# Devi.net
KiCad netlist of a schematic drawn in EAGLE
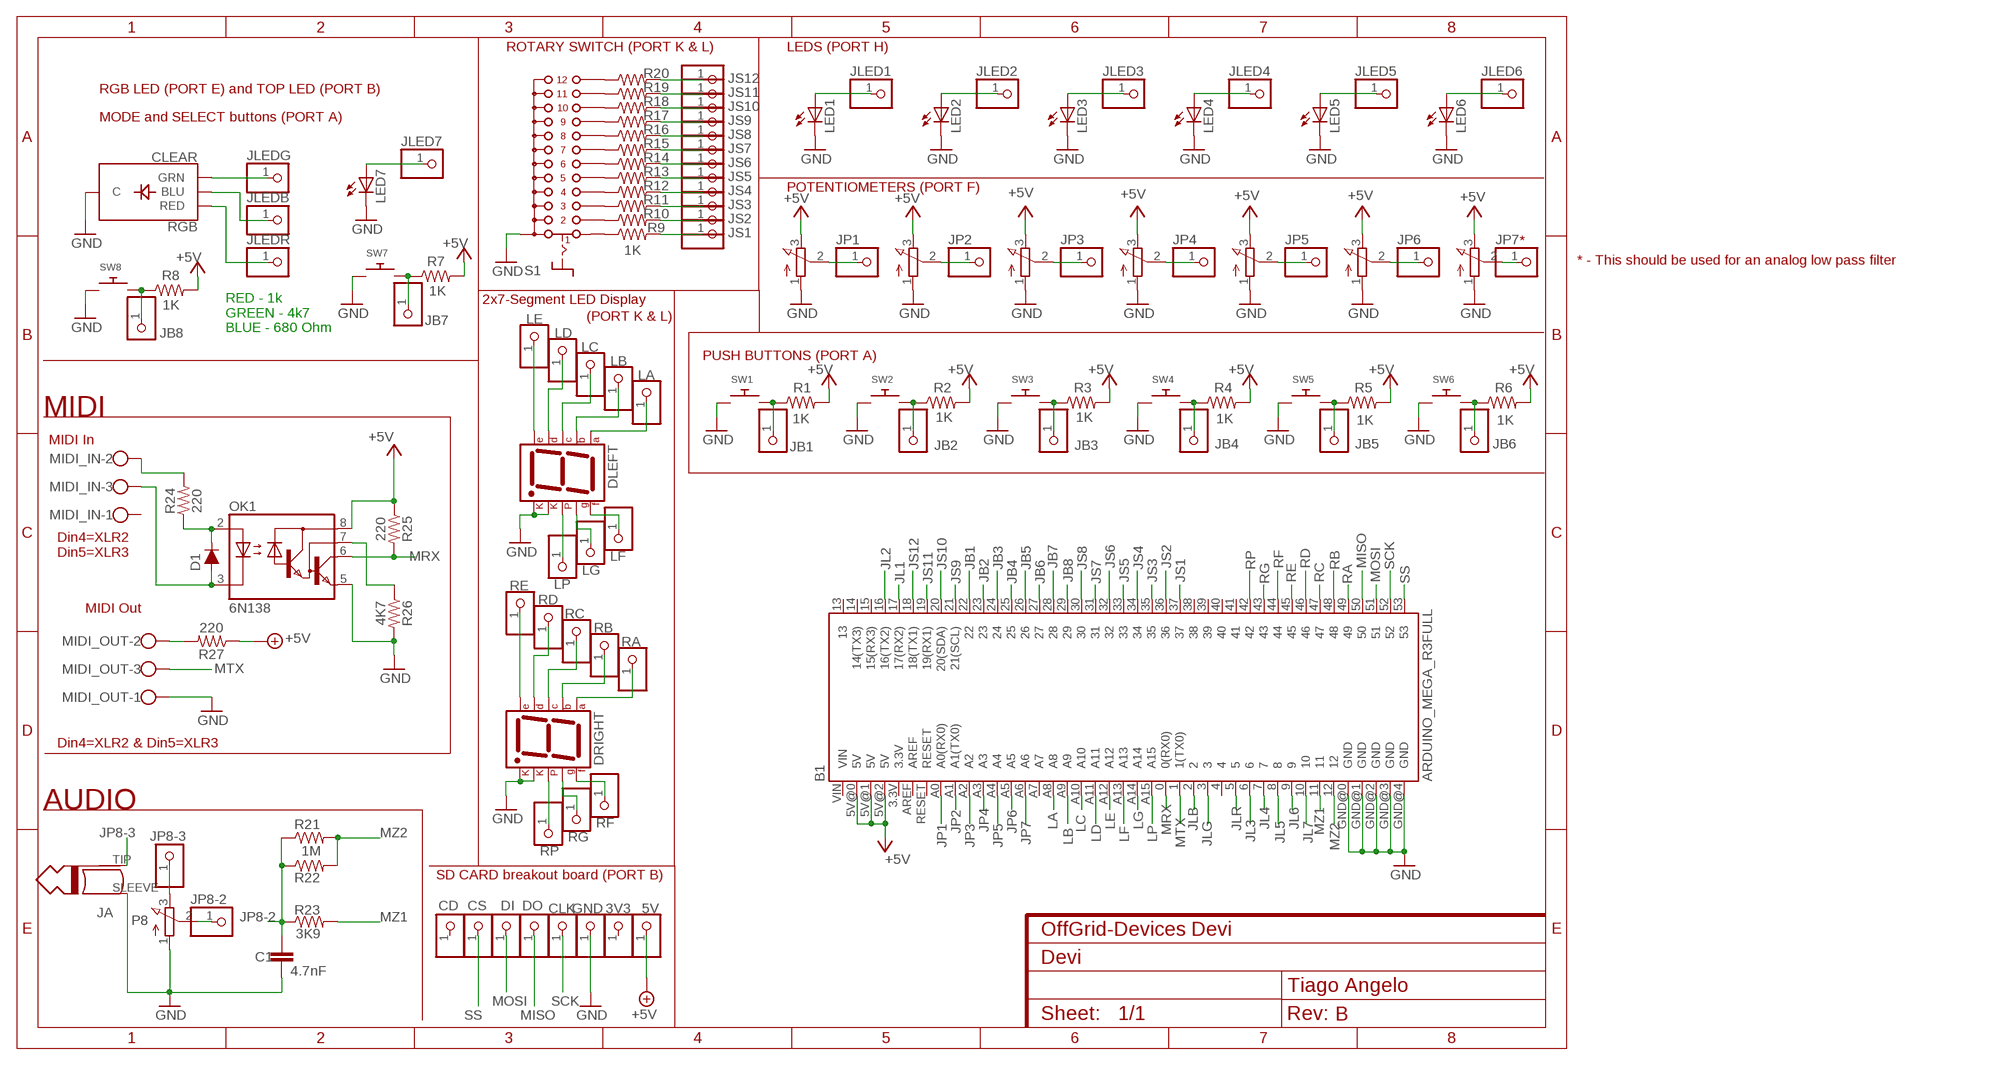
[diagram p0: schematic, sheet 1]

(export (version "E")
  (design (tool "Eeschema 10.0.6"))
  (components
    (comp (ref "3V3")
      (value "PINHD-1X1CB")
      (footprint "eagle-import:1X01-CLEANBIG")
      (libsource (lib "eagle-import") (part "PINHD-1X1CB"))
    )
    (comp (ref "5V")
      (value "PINHD-1X1CB")
      (footprint "eagle-import:1X01-CLEANBIG")
      (libsource (lib "eagle-import") (part "PINHD-1X1CB"))
    )
    (comp (ref "B1")
      (value "ARDUINO_MEGA_R3FULL")
      (footprint "eagle-import:ARDUINO_MEGA")
      (libsource (lib "eagle-import") (part "ARDUINO_MEGA_R3FULL"))
    )
    (comp (ref "C1")
      (value "4.7nF")
      (footprint "eagle-import:C050-025X075")
      (libsource (lib "eagle-import") (part "C-EU050-025X075"))
    )
    (comp (ref "CD")
      (value "PINHD-1X1CB")
      (footprint "eagle-import:1X01-CLEANBIG")
      (libsource (lib "eagle-import") (part "PINHD-1X1CB"))
    )
    (comp (ref "CLK")
      (value "PINHD-1X1CB")
      (footprint "eagle-import:1X01-CLEANBIG")
      (libsource (lib "eagle-import") (part "PINHD-1X1CB"))
    )
    (comp (ref "CS")
      (value "PINHD-1X1CB")
      (footprint "eagle-import:1X01-CLEANBIG")
      (libsource (lib "eagle-import") (part "PINHD-1X1CB"))
    )
    (comp (ref "D1")
      (value "200mA/100V/1V")
      (footprint "eagle-import:DIODE-1N4148")
      (libsource (lib "eagle-import") (part "DIODE-1N4148"))
    )
    (comp (ref "DI")
      (value "PINHD-1X1CB")
      (footprint "eagle-import:1X01-CLEANBIG")
      (libsource (lib "eagle-import") (part "PINHD-1X1CB"))
    )
    (comp (ref "DLEFT")
      (value "7SEG-CK")
      (footprint "eagle-import:7SEG-13")
      (libsource (lib "eagle-import") (part "7SEG-CK"))
    )
    (comp (ref "DO")
      (value "PINHD-1X1CB")
      (footprint "eagle-import:1X01-CLEANBIG")
      (libsource (lib "eagle-import") (part "PINHD-1X1CB"))
    )
    (comp (ref "DRIGHT")
      (value "7SEG-CK")
      (footprint "eagle-import:7SEG-13")
      (libsource (lib "eagle-import") (part "7SEG-CK"))
    )
    (comp (ref "GND")
      (value "PINHD-1X1CB")
      (footprint "eagle-import:1X01-CLEANBIG")
      (libsource (lib "eagle-import") (part "PINHD-1X1CB"))
    )
    (comp (ref "JA")
      (value "MONO_PLUG")
      (footprint "eagle-import:TWO_PADS")
      (libsource (lib "eagle-import") (part "MONO_PLUG"))
    )
    (comp (ref "JB1")
      (value "PINHD-1X1CB")
      (footprint "eagle-import:1X01-CLEANBIG")
      (libsource (lib "eagle-import") (part "PINHD-1X1CB"))
    )
    (comp (ref "JB2")
      (value "PINHD-1X1CB")
      (footprint "eagle-import:1X01-CLEANBIG")
      (libsource (lib "eagle-import") (part "PINHD-1X1CB"))
    )
    (comp (ref "JB3")
      (value "PINHD-1X1CB")
      (footprint "eagle-import:1X01-CLEANBIG")
      (libsource (lib "eagle-import") (part "PINHD-1X1CB"))
    )
    (comp (ref "JB4")
      (value "PINHD-1X1CB")
      (footprint "eagle-import:1X01-CLEANBIG")
      (libsource (lib "eagle-import") (part "PINHD-1X1CB"))
    )
    (comp (ref "JB5")
      (value "PINHD-1X1CB")
      (footprint "eagle-import:1X01-CLEANBIG")
      (libsource (lib "eagle-import") (part "PINHD-1X1CB"))
    )
    (comp (ref "JB6")
      (value "PINHD-1X1CB")
      (footprint "eagle-import:1X01-CLEANBIG")
      (libsource (lib "eagle-import") (part "PINHD-1X1CB"))
    )
    (comp (ref "JB7")
      (value "PINHD-1X1CB")
      (footprint "eagle-import:1X01-CLEANBIG")
      (libsource (lib "eagle-import") (part "PINHD-1X1CB"))
    )
    (comp (ref "JB8")
      (value "PINHD-1X1CB")
      (footprint "eagle-import:1X01-CLEANBIG")
      (libsource (lib "eagle-import") (part "PINHD-1X1CB"))
    )
    (comp (ref "JLED1")
      (value "PINHD-1X1CB")
      (footprint "eagle-import:1X01-CLEANBIG")
      (libsource (lib "eagle-import") (part "PINHD-1X1CB"))
    )
    (comp (ref "JLED2")
      (value "PINHD-1X1CB")
      (footprint "eagle-import:1X01-CLEANBIG")
      (libsource (lib "eagle-import") (part "PINHD-1X1CB"))
    )
    (comp (ref "JLED3")
      (value "PINHD-1X1CB")
      (footprint "eagle-import:1X01-CLEANBIG")
      (libsource (lib "eagle-import") (part "PINHD-1X1CB"))
    )
    (comp (ref "JLED4")
      (value "PINHD-1X1CB")
      (footprint "eagle-import:1X01-CLEANBIG")
      (libsource (lib "eagle-import") (part "PINHD-1X1CB"))
    )
    (comp (ref "JLED5")
      (value "PINHD-1X1CB")
      (footprint "eagle-import:1X01-CLEANBIG")
      (libsource (lib "eagle-import") (part "PINHD-1X1CB"))
    )
    (comp (ref "JLED6")
      (value "PINHD-1X1CB")
      (footprint "eagle-import:1X01-CLEANBIG")
      (libsource (lib "eagle-import") (part "PINHD-1X1CB"))
    )
    (comp (ref "JLED7")
      (value "PINHD-1X1CB")
      (footprint "eagle-import:1X01-CLEANBIG")
      (libsource (lib "eagle-import") (part "PINHD-1X1CB"))
    )
    (comp (ref "JLEDB")
      (value "PINHD-1X1CB")
      (footprint "eagle-import:1X01-CLEANBIG")
      (libsource (lib "eagle-import") (part "PINHD-1X1CB"))
    )
    (comp (ref "JLEDG")
      (value "PINHD-1X1CB")
      (footprint "eagle-import:1X01-CLEANBIG")
      (libsource (lib "eagle-import") (part "PINHD-1X1CB"))
    )
    (comp (ref "JLEDR")
      (value "PINHD-1X1CB")
      (footprint "eagle-import:1X01-CLEANBIG")
      (libsource (lib "eagle-import") (part "PINHD-1X1CB"))
    )
    (comp (ref "JP1")
      (value "PINHD-1X1CB")
      (footprint "eagle-import:1X01-CLEANBIG")
      (libsource (lib "eagle-import") (part "PINHD-1X1CB"))
    )
    (comp (ref "JP2")
      (value "PINHD-1X1CB")
      (footprint "eagle-import:1X01-CLEANBIG")
      (libsource (lib "eagle-import") (part "PINHD-1X1CB"))
    )
    (comp (ref "JP3")
      (value "PINHD-1X1CB")
      (footprint "eagle-import:1X01-CLEANBIG")
      (libsource (lib "eagle-import") (part "PINHD-1X1CB"))
    )
    (comp (ref "JP4")
      (value "PINHD-1X1CB")
      (footprint "eagle-import:1X01-CLEANBIG")
      (libsource (lib "eagle-import") (part "PINHD-1X1CB"))
    )
    (comp (ref "JP5")
      (value "PINHD-1X1CB")
      (footprint "eagle-import:1X01-CLEANBIG")
      (libsource (lib "eagle-import") (part "PINHD-1X1CB"))
    )
    (comp (ref "JP6")
      (value "PINHD-1X1CB")
      (footprint "eagle-import:1X01-CLEANBIG")
      (libsource (lib "eagle-import") (part "PINHD-1X1CB"))
    )
    (comp (ref "JP7")
      (value "PINHD-1X1CB")
      (footprint "eagle-import:1X01-CLEANBIG")
      (libsource (lib "eagle-import") (part "PINHD-1X1CB"))
    )
    (comp (ref "JP8-2")
      (value "PINHD-1X1CB")
      (footprint "eagle-import:1X01-CLEANBIG")
      (libsource (lib "eagle-import") (part "PINHD-1X1CB"))
    )
    (comp (ref "JP8-3")
      (value "PINHD-1X1CB")
      (footprint "eagle-import:1X01-CLEANBIG")
      (libsource (lib "eagle-import") (part "PINHD-1X1CB"))
    )
    (comp (ref "JS1")
      (value "PINHD-1X1CB")
      (footprint "eagle-import:1X01-CLEANBIG")
      (libsource (lib "eagle-import") (part "PINHD-1X1CB"))
    )
    (comp (ref "JS2")
      (value "PINHD-1X1CB")
      (footprint "eagle-import:1X01-CLEANBIG")
      (libsource (lib "eagle-import") (part "PINHD-1X1CB"))
    )
    (comp (ref "JS3")
      (value "PINHD-1X1CB")
      (footprint "eagle-import:1X01-CLEANBIG")
      (libsource (lib "eagle-import") (part "PINHD-1X1CB"))
    )
    (comp (ref "JS4")
      (value "PINHD-1X1CB")
      (footprint "eagle-import:1X01-CLEANBIG")
      (libsource (lib "eagle-import") (part "PINHD-1X1CB"))
    )
    (comp (ref "JS5")
      (value "PINHD-1X1CB")
      (footprint "eagle-import:1X01-CLEANBIG")
      (libsource (lib "eagle-import") (part "PINHD-1X1CB"))
    )
    (comp (ref "JS6")
      (value "PINHD-1X1CB")
      (footprint "eagle-import:1X01-CLEANBIG")
      (libsource (lib "eagle-import") (part "PINHD-1X1CB"))
    )
    (comp (ref "JS7")
      (value "PINHD-1X1CB")
      (footprint "eagle-import:1X01-CLEANBIG")
      (libsource (lib "eagle-import") (part "PINHD-1X1CB"))
    )
    (comp (ref "JS8")
      (value "PINHD-1X1CB")
      (footprint "eagle-import:1X01-CLEANBIG")
      (libsource (lib "eagle-import") (part "PINHD-1X1CB"))
    )
    (comp (ref "JS9")
      (value "PINHD-1X1CB")
      (footprint "eagle-import:1X01-CLEANBIG")
      (libsource (lib "eagle-import") (part "PINHD-1X1CB"))
    )
    (comp (ref "JS10")
      (value "PINHD-1X1CB")
      (footprint "eagle-import:1X01-CLEANBIG")
      (libsource (lib "eagle-import") (part "PINHD-1X1CB"))
    )
    (comp (ref "JS11")
      (value "PINHD-1X1CB")
      (footprint "eagle-import:1X01-CLEANBIG")
      (libsource (lib "eagle-import") (part "PINHD-1X1CB"))
    )
    (comp (ref "JS12")
      (value "PINHD-1X1CB")
      (footprint "eagle-import:1X01-CLEANBIG")
      (libsource (lib "eagle-import") (part "PINHD-1X1CB"))
    )
    (comp (ref "LA")
      (value "PINHD-1X1CB")
      (footprint "eagle-import:1X01-CLEANBIG")
      (libsource (lib "eagle-import") (part "PINHD-1X1CB"))
    )
    (comp (ref "LB")
      (value "PINHD-1X1CB")
      (footprint "eagle-import:1X01-CLEANBIG")
      (libsource (lib "eagle-import") (part "PINHD-1X1CB"))
    )
    (comp (ref "LC")
      (value "PINHD-1X1CB")
      (footprint "eagle-import:1X01-CLEANBIG")
      (libsource (lib "eagle-import") (part "PINHD-1X1CB"))
    )
    (comp (ref "LD")
      (value "PINHD-1X1CB")
      (footprint "eagle-import:1X01-CLEANBIG")
      (libsource (lib "eagle-import") (part "PINHD-1X1CB"))
    )
    (comp (ref "LE")
      (value "PINHD-1X1CB")
      (footprint "eagle-import:1X01-CLEANBIG")
      (libsource (lib "eagle-import") (part "PINHD-1X1CB"))
    )
    (comp (ref "LED1")
      (value "LED3MM")
      (footprint "eagle-import:LED3MM")
      (libsource (lib "eagle-import") (part "LED3MM"))
    )
    (comp (ref "LED2")
      (value "LED3MM")
      (footprint "eagle-import:LED3MM")
      (libsource (lib "eagle-import") (part "LED3MM"))
    )
    (comp (ref "LED3")
      (value "LED3MM")
      (footprint "eagle-import:LED3MM")
      (libsource (lib "eagle-import") (part "LED3MM"))
    )
    (comp (ref "LED4")
      (value "LED3MM")
      (footprint "eagle-import:LED3MM")
      (libsource (lib "eagle-import") (part "LED3MM"))
    )
    (comp (ref "LED5")
      (value "LED3MM")
      (footprint "eagle-import:LED3MM")
      (libsource (lib "eagle-import") (part "LED3MM"))
    )
    (comp (ref "LED6")
      (value "LED3MM")
      (footprint "eagle-import:LED3MM")
      (libsource (lib "eagle-import") (part "LED3MM"))
    )
    (comp (ref "LED7")
      (value "LED3MM")
      (footprint "eagle-import:LED3MM")
      (libsource (lib "eagle-import") (part "LED3MM"))
    )
    (comp (ref "LF")
      (value "PINHD-1X1CB")
      (footprint "eagle-import:1X01-CLEANBIG")
      (libsource (lib "eagle-import") (part "PINHD-1X1CB"))
    )
    (comp (ref "LG")
      (value "PINHD-1X1CB")
      (footprint "eagle-import:1X01-CLEANBIG")
      (libsource (lib "eagle-import") (part "PINHD-1X1CB"))
    )
    (comp (ref "LP")
      (value "PINHD-1X1CB")
      (footprint "eagle-import:1X01-CLEANBIG")
      (libsource (lib "eagle-import") (part "PINHD-1X1CB"))
    )
    (comp (ref "MIDI_IN")
      (value "W237-103")
      (footprint "eagle-import:W237-103")
      (fields (field (name "MPN") "237-103"))
      (libsource (lib "eagle-import") (part "W237-103"))
    )
    (comp (ref "MIDI_OUT")
      (value "W237-103")
      (footprint "eagle-import:W237-103")
      (fields (field (name "MPN") "237-103"))
      (libsource (lib "eagle-import") (part "W237-103"))
    )
    (comp (ref "OK1")
      (value "6N138")
      (footprint "eagle-import:DIL08")
      (fields (field (name "MF") "VISHAY/TELEFUNKEN"))
      (libsource (lib "eagle-import") (part "6N138"))
    )
    (comp (ref "P1")
      (value "3RP/1610N")
      (footprint "eagle-import:3RP_1610N")
      (libsource (lib "eagle-import") (part "3RP/1610N"))
    )
    (comp (ref "P2")
      (value "3RP/1610N")
      (footprint "eagle-import:3RP_1610N")
      (libsource (lib "eagle-import") (part "3RP/1610N"))
    )
    (comp (ref "P3")
      (value "3RP/1610N")
      (footprint "eagle-import:3RP_1610N")
      (libsource (lib "eagle-import") (part "3RP/1610N"))
    )
    (comp (ref "P4")
      (value "3RP/1610N")
      (footprint "eagle-import:3RP_1610N")
      (libsource (lib "eagle-import") (part "3RP/1610N"))
    )
    (comp (ref "P5")
      (value "3RP/1610N")
      (footprint "eagle-import:3RP_1610N")
      (libsource (lib "eagle-import") (part "3RP/1610N"))
    )
    (comp (ref "P6")
      (value "3RP/1610N")
      (footprint "eagle-import:3RP_1610N")
      (libsource (lib "eagle-import") (part "3RP/1610N"))
    )
    (comp (ref "P7")
      (value "3RP/1610N")
      (footprint "eagle-import:3RP_1610N")
      (libsource (lib "eagle-import") (part "3RP/1610N"))
    )
    (comp (ref "P8")
      (value "3RP/1610N")
      (footprint "eagle-import:3RP_1610N")
      (libsource (lib "eagle-import") (part "3RP/1610N"))
    )
    (comp (ref "R1")
      (value "1K")
      (footprint "eagle-import:AXIAL-0.3")
      (libsource (lib "eagle-import") (part "1KOHM-HORIZ-1/4W-5%"))
    )
    (comp (ref "R2")
      (value "1K")
      (footprint "eagle-import:AXIAL-0.3")
      (libsource (lib "eagle-import") (part "1KOHM-HORIZ-1/4W-5%"))
    )
    (comp (ref "R3")
      (value "1K")
      (footprint "eagle-import:AXIAL-0.3")
      (libsource (lib "eagle-import") (part "1KOHM-HORIZ-1/4W-5%"))
    )
    (comp (ref "R4")
      (value "1K")
      (footprint "eagle-import:AXIAL-0.3")
      (libsource (lib "eagle-import") (part "1KOHM-HORIZ-1/4W-5%"))
    )
    (comp (ref "R5")
      (value "1K")
      (footprint "eagle-import:AXIAL-0.3")
      (libsource (lib "eagle-import") (part "1KOHM-HORIZ-1/4W-5%"))
    )
    (comp (ref "R6")
      (value "1K")
      (footprint "eagle-import:AXIAL-0.3")
      (libsource (lib "eagle-import") (part "1KOHM-HORIZ-1/4W-5%"))
    )
    (comp (ref "R7")
      (value "1K")
      (footprint "eagle-import:AXIAL-0.3")
      (libsource (lib "eagle-import") (part "1KOHM-HORIZ-1/4W-5%"))
    )
    (comp (ref "R8")
      (value "1K")
      (footprint "eagle-import:AXIAL-0.3")
      (libsource (lib "eagle-import") (part "1KOHM-HORIZ-1/4W-5%"))
    )
    (comp (ref "R9")
      (value "1K")
      (footprint "eagle-import:AXIAL-0.3")
      (libsource (lib "eagle-import") (part "1KOHM-HORIZ-1/4W-5%"))
    )
    (comp (ref "R10")
      (value "1K")
      (footprint "eagle-import:AXIAL-0.3")
      (libsource (lib "eagle-import") (part "1KOHM-HORIZ-1/4W-5%"))
    )
    (comp (ref "R11")
      (value "1K")
      (footprint "eagle-import:AXIAL-0.3")
      (libsource (lib "eagle-import") (part "1KOHM-HORIZ-1/4W-5%"))
    )
    (comp (ref "R12")
      (value "1K")
      (footprint "eagle-import:AXIAL-0.3")
      (libsource (lib "eagle-import") (part "1KOHM-HORIZ-1/4W-5%"))
    )
    (comp (ref "R13")
      (value "1K")
      (footprint "eagle-import:AXIAL-0.3")
      (libsource (lib "eagle-import") (part "1KOHM-HORIZ-1/4W-5%"))
    )
    (comp (ref "R14")
      (value "1K")
      (footprint "eagle-import:AXIAL-0.3")
      (libsource (lib "eagle-import") (part "1KOHM-HORIZ-1/4W-5%"))
    )
    (comp (ref "R15")
      (value "1K")
      (footprint "eagle-import:AXIAL-0.3")
      (libsource (lib "eagle-import") (part "1KOHM-HORIZ-1/4W-5%"))
    )
    (comp (ref "R16")
      (value "1K")
      (footprint "eagle-import:AXIAL-0.3")
      (libsource (lib "eagle-import") (part "1KOHM-HORIZ-1/4W-5%"))
    )
    (comp (ref "R17")
      (value "1K")
      (footprint "eagle-import:AXIAL-0.3")
      (libsource (lib "eagle-import") (part "1KOHM-HORIZ-1/4W-5%"))
    )
    (comp (ref "R18")
      (value "1K")
      (footprint "eagle-import:AXIAL-0.3")
      (libsource (lib "eagle-import") (part "1KOHM-HORIZ-1/4W-5%"))
    )
    (comp (ref "R19")
      (value "1K")
      (footprint "eagle-import:AXIAL-0.3")
      (libsource (lib "eagle-import") (part "1KOHM-HORIZ-1/4W-5%"))
    )
    (comp (ref "R20")
      (value "1K")
      (footprint "eagle-import:AXIAL-0.3")
      (libsource (lib "eagle-import") (part "1KOHM-HORIZ-1/4W-5%"))
    )
    (comp (ref "R21")
      (value "1M")
      (footprint "eagle-import:AXIAL-0.3")
      (libsource (lib "eagle-import") (part "1KOHM-HORIZ-1/4W-5%"))
    )
    (comp (ref "R22")
      (value "1M")
      (footprint "eagle-import:AXIAL-0.3")
      (libsource (lib "eagle-import") (part "1KOHM-HORIZ-1/4W-5%"))
    )
    (comp (ref "R23")
      (value "3K9")
      (footprint "eagle-import:AXIAL-0.3")
      (libsource (lib "eagle-import") (part "1KOHM-HORIZ-1/4W-5%"))
    )
    (comp (ref "R24")
      (value "220")
      (footprint "eagle-import:AXIAL-0.3")
      (libsource (lib "eagle-import") (part "1KOHM-HORIZ-1/4W-5%"))
    )
    (comp (ref "R25")
      (value "220")
      (footprint "eagle-import:AXIAL-0.3")
      (libsource (lib "eagle-import") (part "1KOHM-HORIZ-1/4W-5%"))
    )
    (comp (ref "R26")
      (value "4K7")
      (footprint "eagle-import:AXIAL-0.3")
      (libsource (lib "eagle-import") (part "1KOHM-HORIZ-1/4W-5%"))
    )
    (comp (ref "R27")
      (value "220")
      (footprint "eagle-import:AXIAL-0.3")
      (libsource (lib "eagle-import") (part "1KOHM-HORIZ-1/4W-5%"))
    )
    (comp (ref "RA")
      (value "PINHD-1X1CB")
      (footprint "eagle-import:1X01-CLEANBIG")
      (libsource (lib "eagle-import") (part "PINHD-1X1CB"))
    )
    (comp (ref "RB")
      (value "PINHD-1X1CB")
      (footprint "eagle-import:1X01-CLEANBIG")
      (libsource (lib "eagle-import") (part "PINHD-1X1CB"))
    )
    (comp (ref "RC")
      (value "PINHD-1X1CB")
      (footprint "eagle-import:1X01-CLEANBIG")
      (libsource (lib "eagle-import") (part "PINHD-1X1CB"))
    )
    (comp (ref "RD")
      (value "PINHD-1X1CB")
      (footprint "eagle-import:1X01-CLEANBIG")
      (libsource (lib "eagle-import") (part "PINHD-1X1CB"))
    )
    (comp (ref "RE")
      (value "PINHD-1X1CB")
      (footprint "eagle-import:1X01-CLEANBIG")
      (libsource (lib "eagle-import") (part "PINHD-1X1CB"))
    )
    (comp (ref "RF")
      (value "PINHD-1X1CB")
      (footprint "eagle-import:1X01-CLEANBIG")
      (libsource (lib "eagle-import") (part "PINHD-1X1CB"))
    )
    (comp (ref "RG")
      (value "PINHD-1X1CB")
      (footprint "eagle-import:1X01-CLEANBIG")
      (libsource (lib "eagle-import") (part "PINHD-1X1CB"))
    )
    (comp (ref "RGB")
      (value "CLEAR")
      (footprint "eagle-import:LED-RGB-THRU")
      (libsource (lib "eagle-import") (part "LED-RGB-CCCLEAR"))
    )
    (comp (ref "RP")
      (value "PINHD-1X1CB")
      (footprint "eagle-import:1X01-CLEANBIG")
      (libsource (lib "eagle-import") (part "PINHD-1X1CB"))
    )
    (comp (ref "S1")
      (value "CK101X12")
      (footprint "eagle-import:CK101X12")
      (libsource (lib "eagle-import") (part "CK101X12"))
    )
    (comp (ref "SW1")
      (value "SWITCH_PUSHBUTTONEVQ-PE")
      (footprint "eagle-import:TACT_PANA-EVQ")
      (libsource (lib "eagle-import") (part "SWITCH_PUSHBUTTONEVQ-PE"))
    )
    (comp (ref "SW2")
      (value "SWITCH_PUSHBUTTONEVQ-PE")
      (footprint "eagle-import:TACT_PANA-EVQ")
      (libsource (lib "eagle-import") (part "SWITCH_PUSHBUTTONEVQ-PE"))
    )
    (comp (ref "SW3")
      (value "SWITCH_PUSHBUTTONEVQ-PE")
      (footprint "eagle-import:TACT_PANA-EVQ")
      (libsource (lib "eagle-import") (part "SWITCH_PUSHBUTTONEVQ-PE"))
    )
    (comp (ref "SW4")
      (value "SWITCH_PUSHBUTTONEVQ-PE")
      (footprint "eagle-import:TACT_PANA-EVQ")
      (libsource (lib "eagle-import") (part "SWITCH_PUSHBUTTONEVQ-PE"))
    )
    (comp (ref "SW5")
      (value "SWITCH_PUSHBUTTONEVQ-PE")
      (footprint "eagle-import:TACT_PANA-EVQ")
      (libsource (lib "eagle-import") (part "SWITCH_PUSHBUTTONEVQ-PE"))
    )
    (comp (ref "SW6")
      (value "SWITCH_PUSHBUTTONEVQ-PE")
      (footprint "eagle-import:TACT_PANA-EVQ")
      (libsource (lib "eagle-import") (part "SWITCH_PUSHBUTTONEVQ-PE"))
    )
    (comp (ref "SW7")
      (value "SWITCH_PUSHBUTTONEVQ-PE")
      (footprint "eagle-import:TACT_PANA-EVQ")
      (libsource (lib "eagle-import") (part "SWITCH_PUSHBUTTONEVQ-PE"))
    )
    (comp (ref "SW8")
      (value "SWITCH_PUSHBUTTONEVQ-PE")
      (footprint "eagle-import:TACT_PANA-EVQ")
      (libsource (lib "eagle-import") (part "SWITCH_PUSHBUTTONEVQ-PE"))
    )
  )
  (nets
    (net (code "1") (name "+5V") (class "Default")
      (node (ref "5V") (pin "1") (pinfunction "1_1") (pintype "passive"))
      (node (ref "B1") (pin "5V@0") (pinfunction "5V_5V@0") (pintype "bidirectional"))
      (node (ref "B1") (pin "5V@1") (pinfunction "5V_5V@1") (pintype "bidirectional"))
      (node (ref "B1") (pin "5V@2") (pinfunction "5V_5V@2") (pintype "bidirectional"))
      (node (ref "OK1") (pin "8") (pinfunction "VCC_8") (pintype "passive"))
      (node (ref "P1") (pin "3") (pinfunction "E_3") (pintype "passive"))
      (node (ref "P2") (pin "3") (pinfunction "E_3") (pintype "passive"))
      (node (ref "P3") (pin "3") (pinfunction "E_3") (pintype "passive"))
      (node (ref "P4") (pin "3") (pinfunction "E_3") (pintype "passive"))
      (node (ref "P5") (pin "3") (pinfunction "E_3") (pintype "passive"))
      (node (ref "P6") (pin "3") (pinfunction "E_3") (pintype "passive"))
      (node (ref "P7") (pin "3") (pinfunction "E_3") (pintype "passive"))
      (node (ref "R1") (pin "P$2") (pinfunction "2_P$2") (pintype "passive"))
      (node (ref "R2") (pin "P$2") (pinfunction "2_P$2") (pintype "passive"))
      (node (ref "R25") (pin "P$1") (pinfunction "1_P$1") (pintype "passive"))
      (node (ref "R27") (pin "P$1") (pinfunction "1_P$1") (pintype "passive"))
      (node (ref "R3") (pin "P$2") (pinfunction "2_P$2") (pintype "passive"))
      (node (ref "R4") (pin "P$2") (pinfunction "2_P$2") (pintype "passive"))
      (node (ref "R5") (pin "P$2") (pinfunction "2_P$2") (pintype "passive"))
      (node (ref "R6") (pin "P$2") (pinfunction "2_P$2") (pintype "passive"))
      (node (ref "R7") (pin "P$2") (pinfunction "2_P$2") (pintype "passive"))
      (node (ref "R8") (pin "P$2") (pinfunction "2_P$2") (pintype "passive"))
    )
    (net (code "2") (name "/JB1") (class "Default")
      (node (ref "B1") (pin "22") (pinfunction "22_22") (pintype "bidirectional"))
      (node (ref "JB1") (pin "1") (pinfunction "1_1") (pintype "passive"))
      (node (ref "R1") (pin "P$1") (pinfunction "1_P$1") (pintype "passive"))
      (node (ref "SW1") (pin "P$2") (pinfunction "P$2_P$2") (pintype "passive"))
    )
    (net (code "3") (name "/JB2") (class "Default")
      (node (ref "B1") (pin "23") (pinfunction "23_23") (pintype "bidirectional"))
      (node (ref "JB2") (pin "1") (pinfunction "1_1") (pintype "passive"))
      (node (ref "R2") (pin "P$1") (pinfunction "1_P$1") (pintype "passive"))
      (node (ref "SW2") (pin "P$2") (pinfunction "P$2_P$2") (pintype "passive"))
    )
    (net (code "4") (name "/JB3") (class "Default")
      (node (ref "B1") (pin "24") (pinfunction "24_24") (pintype "bidirectional"))
      (node (ref "JB3") (pin "1") (pinfunction "1_1") (pintype "passive"))
      (node (ref "R3") (pin "P$1") (pinfunction "1_P$1") (pintype "passive"))
      (node (ref "SW3") (pin "P$2") (pinfunction "P$2_P$2") (pintype "passive"))
    )
    (net (code "5") (name "/JB4") (class "Default")
      (node (ref "B1") (pin "25") (pinfunction "25_25") (pintype "bidirectional"))
      (node (ref "JB4") (pin "1") (pinfunction "1_1") (pintype "passive"))
      (node (ref "R4") (pin "P$1") (pinfunction "1_P$1") (pintype "passive"))
      (node (ref "SW4") (pin "P$2") (pinfunction "P$2_P$2") (pintype "passive"))
    )
    (net (code "6") (name "/JB5") (class "Default")
      (node (ref "B1") (pin "26") (pinfunction "26_26") (pintype "bidirectional"))
      (node (ref "JB5") (pin "1") (pinfunction "1_1") (pintype "passive"))
      (node (ref "R5") (pin "P$1") (pinfunction "1_P$1") (pintype "passive"))
      (node (ref "SW5") (pin "P$2") (pinfunction "P$2_P$2") (pintype "passive"))
    )
    (net (code "7") (name "/JB6") (class "Default")
      (node (ref "B1") (pin "27") (pinfunction "27_27") (pintype "bidirectional"))
      (node (ref "JB6") (pin "1") (pinfunction "1_1") (pintype "passive"))
      (node (ref "R6") (pin "P$1") (pinfunction "1_P$1") (pintype "passive"))
      (node (ref "SW6") (pin "P$2") (pinfunction "P$2_P$2") (pintype "passive"))
    )
    (net (code "8") (name "/JB7") (class "Default")
      (node (ref "B1") (pin "28") (pinfunction "28_28") (pintype "bidirectional"))
      (node (ref "JB7") (pin "1") (pinfunction "1_1") (pintype "passive"))
      (node (ref "R7") (pin "P$1") (pinfunction "1_P$1") (pintype "passive"))
      (node (ref "SW7") (pin "P$2") (pinfunction "P$2_P$2") (pintype "passive"))
    )
    (net (code "9") (name "/JB8") (class "Default")
      (node (ref "B1") (pin "29") (pinfunction "29_29") (pintype "bidirectional"))
      (node (ref "JB8") (pin "1") (pinfunction "1_1") (pintype "passive"))
      (node (ref "R8") (pin "P$1") (pinfunction "1_P$1") (pintype "passive"))
      (node (ref "SW8") (pin "P$2") (pinfunction "P$2_P$2") (pintype "passive"))
    )
    (net (code "10") (name "/JL1") (class "Default")
      (node (ref "B1") (pin "17") (pinfunction "17(RX2)_17") (pintype "bidirectional"))
      (node (ref "JLED1") (pin "1") (pinfunction "1_1") (pintype "passive"))
      (node (ref "LED1") (pin "A") (pinfunction "A_A") (pintype "passive"))
    )
    (net (code "11") (name "/JL2") (class "Default")
      (node (ref "B1") (pin "16") (pinfunction "16(TX2)_16") (pintype "bidirectional"))
      (node (ref "JLED2") (pin "1") (pinfunction "1_1") (pintype "passive"))
      (node (ref "LED2") (pin "A") (pinfunction "A_A") (pintype "passive"))
    )
    (net (code "12") (name "/JL3") (class "Default")
      (node (ref "B1") (pin "6") (pinfunction "6_6") (pintype "bidirectional"))
      (node (ref "JLED3") (pin "1") (pinfunction "1_1") (pintype "passive"))
      (node (ref "LED3") (pin "A") (pinfunction "A_A") (pintype "passive"))
    )
    (net (code "13") (name "/JL4") (class "Default")
      (node (ref "B1") (pin "7") (pinfunction "7_7") (pintype "bidirectional"))
      (node (ref "JLED4") (pin "1") (pinfunction "1_1") (pintype "passive"))
      (node (ref "LED4") (pin "A") (pinfunction "A_A") (pintype "passive"))
    )
    (net (code "14") (name "/JL5") (class "Default")
      (node (ref "B1") (pin "8") (pinfunction "8_8") (pintype "bidirectional"))
      (node (ref "JLED5") (pin "1") (pinfunction "1_1") (pintype "passive"))
      (node (ref "LED5") (pin "A") (pinfunction "A_A") (pintype "passive"))
    )
    (net (code "15") (name "/JL6") (class "Default")
      (node (ref "B1") (pin "9") (pinfunction "9_9") (pintype "bidirectional"))
      (node (ref "JLED6") (pin "1") (pinfunction "1_1") (pintype "passive"))
      (node (ref "LED6") (pin "A") (pinfunction "A_A") (pintype "passive"))
    )
    (net (code "16") (name "/JL7") (class "Default")
      (node (ref "B1") (pin "10") (pinfunction "10_10") (pintype "bidirectional"))
      (node (ref "JLED7") (pin "1") (pinfunction "1_1") (pintype "passive"))
      (node (ref "LED7") (pin "A") (pinfunction "A_A") (pintype "passive"))
    )
    (net (code "17") (name "/JLB") (class "Default")
      (node (ref "B1") (pin "2") (pinfunction "2_2") (pintype "bidirectional"))
      (node (ref "JLEDB") (pin "1") (pinfunction "1_1") (pintype "passive"))
      (node (ref "RGB") (pin "4") (pinfunction "BLU_4") (pintype "bidirectional"))
    )
    (net (code "18") (name "/JLG") (class "Default")
      (node (ref "B1") (pin "3") (pinfunction "3_3") (pintype "bidirectional"))
      (node (ref "JLEDG") (pin "1") (pinfunction "1_1") (pintype "passive"))
      (node (ref "RGB") (pin "3") (pinfunction "GRN_3") (pintype "bidirectional"))
    )
    (net (code "19") (name "/JLR") (class "Default")
      (node (ref "B1") (pin "5") (pinfunction "5_5") (pintype "bidirectional"))
      (node (ref "JLEDR") (pin "1") (pinfunction "1_1") (pintype "passive"))
      (node (ref "RGB") (pin "1") (pinfunction "RED_1") (pintype "bidirectional"))
    )
    (net (code "20") (name "/JP1") (class "Default")
      (node (ref "B1") (pin "A0") (pinfunction "A0(RX0)_A0") (pintype "bidirectional"))
      (node (ref "JP1") (pin "1") (pinfunction "1_1") (pintype "passive"))
      (node (ref "P1") (pin "2") (pinfunction "S_2") (pintype "passive"))
    )
    (net (code "21") (name "/JP2") (class "Default")
      (node (ref "B1") (pin "A1") (pinfunction "A1(TX0)_A1") (pintype "bidirectional"))
      (node (ref "JP2") (pin "1") (pinfunction "1_1") (pintype "passive"))
      (node (ref "P2") (pin "2") (pinfunction "S_2") (pintype "passive"))
    )
    (net (code "22") (name "/JP3") (class "Default")
      (node (ref "B1") (pin "A2") (pinfunction "A2_A2") (pintype "bidirectional"))
      (node (ref "JP3") (pin "1") (pinfunction "1_1") (pintype "passive"))
      (node (ref "P3") (pin "2") (pinfunction "S_2") (pintype "passive"))
    )
    (net (code "23") (name "/JP4") (class "Default")
      (node (ref "B1") (pin "A3") (pinfunction "A3_A3") (pintype "bidirectional"))
      (node (ref "JP4") (pin "1") (pinfunction "1_1") (pintype "passive"))
      (node (ref "P4") (pin "2") (pinfunction "S_2") (pintype "passive"))
    )
    (net (code "24") (name "/JP5") (class "Default")
      (node (ref "B1") (pin "A4") (pinfunction "A4_A4") (pintype "bidirectional"))
      (node (ref "JP5") (pin "1") (pinfunction "1_1") (pintype "passive"))
      (node (ref "P5") (pin "2") (pinfunction "S_2") (pintype "passive"))
    )
    (net (code "25") (name "/JP6") (class "Default")
      (node (ref "B1") (pin "A5") (pinfunction "A5_A5") (pintype "bidirectional"))
      (node (ref "JP6") (pin "1") (pinfunction "1_1") (pintype "passive"))
      (node (ref "P6") (pin "2") (pinfunction "S_2") (pintype "passive"))
    )
    (net (code "26") (name "/JP7") (class "Default")
      (node (ref "B1") (pin "A6") (pinfunction "A6_A6") (pintype "bidirectional"))
      (node (ref "JP7") (pin "1") (pinfunction "1_1") (pintype "passive"))
      (node (ref "P7") (pin "2") (pinfunction "S_2") (pintype "passive"))
    )
    (net (code "27") (name "/JP8-2") (class "Default")
      (node (ref "C1") (pin "1") (pinfunction "1_1") (pintype "passive"))
      (node (ref "JP8-2") (pin "1") (pinfunction "1_1") (pintype "passive"))
      (node (ref "P8") (pin "2") (pinfunction "S_2") (pintype "passive"))
      (node (ref "R21") (pin "P$1") (pinfunction "1_P$1") (pintype "passive"))
      (node (ref "R22") (pin "P$1") (pinfunction "1_P$1") (pintype "passive"))
      (node (ref "R23") (pin "P$1") (pinfunction "1_P$1") (pintype "passive"))
    )
    (net (code "28") (name "/JP8-3") (class "Default")
      (node (ref "JA") (pin "TIP") (pinfunction "TIP_TIP") (pintype "passive"))
      (node (ref "JP8-3") (pin "1") (pinfunction "1_1") (pintype "passive"))
      (node (ref "P8") (pin "3") (pinfunction "E_3") (pintype "passive"))
    )
    (net (code "29") (name "/JS1") (class "Default")
      (node (ref "B1") (pin "37") (pinfunction "37_37") (pintype "bidirectional"))
      (node (ref "JS1") (pin "1") (pinfunction "1_1") (pintype "passive"))
      (node (ref "R9") (pin "P$2") (pinfunction "2_P$2") (pintype "passive"))
    )
    (net (code "30") (name "/JS2") (class "Default")
      (node (ref "B1") (pin "36") (pinfunction "36_36") (pintype "bidirectional"))
      (node (ref "JS2") (pin "1") (pinfunction "1_1") (pintype "passive"))
      (node (ref "R10") (pin "P$2") (pinfunction "2_P$2") (pintype "passive"))
    )
    (net (code "31") (name "/JS3") (class "Default")
      (node (ref "B1") (pin "35") (pinfunction "35_35") (pintype "bidirectional"))
      (node (ref "JS3") (pin "1") (pinfunction "1_1") (pintype "passive"))
      (node (ref "R11") (pin "P$2") (pinfunction "2_P$2") (pintype "passive"))
    )
    (net (code "32") (name "/JS4") (class "Default")
      (node (ref "B1") (pin "34") (pinfunction "34_34") (pintype "bidirectional"))
      (node (ref "JS4") (pin "1") (pinfunction "1_1") (pintype "passive"))
      (node (ref "R12") (pin "P$2") (pinfunction "2_P$2") (pintype "passive"))
    )
    (net (code "33") (name "/JS5") (class "Default")
      (node (ref "B1") (pin "33") (pinfunction "33_33") (pintype "bidirectional"))
      (node (ref "JS5") (pin "1") (pinfunction "1_1") (pintype "passive"))
      (node (ref "R13") (pin "P$2") (pinfunction "2_P$2") (pintype "passive"))
    )
    (net (code "34") (name "/JS6") (class "Default")
      (node (ref "B1") (pin "32") (pinfunction "32_32") (pintype "bidirectional"))
      (node (ref "JS6") (pin "1") (pinfunction "1_1") (pintype "passive"))
      (node (ref "R14") (pin "P$2") (pinfunction "2_P$2") (pintype "passive"))
    )
    (net (code "35") (name "/JS7") (class "Default")
      (node (ref "B1") (pin "31") (pinfunction "31_31") (pintype "bidirectional"))
      (node (ref "JS7") (pin "1") (pinfunction "1_1") (pintype "passive"))
      (node (ref "R15") (pin "P$2") (pinfunction "2_P$2") (pintype "passive"))
    )
    (net (code "36") (name "/JS8") (class "Default")
      (node (ref "B1") (pin "30") (pinfunction "30_30") (pintype "bidirectional"))
      (node (ref "JS8") (pin "1") (pinfunction "1_1") (pintype "passive"))
      (node (ref "R16") (pin "P$2") (pinfunction "2_P$2") (pintype "passive"))
    )
    (net (code "37") (name "/JS9") (class "Default")
      (node (ref "B1") (pin "21") (pinfunction "21(SCL)_21") (pintype "bidirectional"))
      (node (ref "JS9") (pin "1") (pinfunction "1_1") (pintype "passive"))
      (node (ref "R17") (pin "P$2") (pinfunction "2_P$2") (pintype "passive"))
    )
    (net (code "38") (name "/JS10") (class "Default")
      (node (ref "B1") (pin "20") (pinfunction "20(SDA)_20") (pintype "bidirectional"))
      (node (ref "JS10") (pin "1") (pinfunction "1_1") (pintype "passive"))
      (node (ref "R18") (pin "P$2") (pinfunction "2_P$2") (pintype "passive"))
    )
    (net (code "39") (name "/JS11") (class "Default")
      (node (ref "B1") (pin "19") (pinfunction "19(RX1)_19") (pintype "bidirectional"))
      (node (ref "JS11") (pin "1") (pinfunction "1_1") (pintype "passive"))
      (node (ref "R19") (pin "P$2") (pinfunction "2_P$2") (pintype "passive"))
    )
    (net (code "40") (name "/JS12") (class "Default")
      (node (ref "B1") (pin "18") (pinfunction "18(TX1)_18") (pintype "bidirectional"))
      (node (ref "JS12") (pin "1") (pinfunction "1_1") (pintype "passive"))
      (node (ref "R20") (pin "P$2") (pinfunction "2_P$2") (pintype "passive"))
    )
    (net (code "41") (name "/LA") (class "Default")
      (node (ref "B1") (pin "A8") (pinfunction "A8_A8") (pintype "bidirectional"))
      (node (ref "DLEFT") (pin "7") (pinfunction "A_7") (pintype "passive"))
      (node (ref "LA") (pin "1") (pinfunction "1_1") (pintype "passive"))
    )
    (net (code "42") (name "/LB") (class "Default")
      (node (ref "B1") (pin "A9") (pinfunction "A9_A9") (pintype "bidirectional"))
      (node (ref "DLEFT") (pin "6") (pinfunction "B_6") (pintype "passive"))
      (node (ref "LB") (pin "1") (pinfunction "1_1") (pintype "passive"))
    )
    (net (code "43") (name "/LC") (class "Default")
      (node (ref "B1") (pin "A10") (pinfunction "A10_A10") (pintype "bidirectional"))
      (node (ref "DLEFT") (pin "4") (pinfunction "C_4") (pintype "passive"))
      (node (ref "LC") (pin "1") (pinfunction "1_1") (pintype "passive"))
    )
    (net (code "44") (name "/LD") (class "Default")
      (node (ref "B1") (pin "A11") (pinfunction "A11_A11") (pintype "bidirectional"))
      (node (ref "DLEFT") (pin "2") (pinfunction "D_2") (pintype "passive"))
      (node (ref "LD") (pin "1") (pinfunction "1_1") (pintype "passive"))
    )
    (net (code "45") (name "/LE") (class "Default")
      (node (ref "B1") (pin "A12") (pinfunction "A12_A12") (pintype "bidirectional"))
      (node (ref "DLEFT") (pin "1") (pinfunction "E_1") (pintype "passive"))
      (node (ref "LE") (pin "1") (pinfunction "1_1") (pintype "passive"))
    )
    (net (code "46") (name "/LF") (class "Default")
      (node (ref "B1") (pin "A13") (pinfunction "A13_A13") (pintype "bidirectional"))
      (node (ref "DLEFT") (pin "9") (pinfunction "F_9") (pintype "passive"))
      (node (ref "LF") (pin "1") (pinfunction "1_1") (pintype "passive"))
    )
    (net (code "47") (name "/LG") (class "Default")
      (node (ref "B1") (pin "A14") (pinfunction "A14_A14") (pintype "bidirectional"))
      (node (ref "DLEFT") (pin "10") (pinfunction "G_10") (pintype "passive"))
      (node (ref "LG") (pin "1") (pinfunction "1_1") (pintype "passive"))
    )
    (net (code "48") (name "/LP") (class "Default")
      (node (ref "B1") (pin "A15") (pinfunction "A15_A15") (pintype "bidirectional"))
      (node (ref "DLEFT") (pin "5") (pinfunction "DP_5") (pintype "passive"))
      (node (ref "LP") (pin "1") (pinfunction "1_1") (pintype "passive"))
    )
    (net (code "49") (name "/MISO") (class "Default")
      (node (ref "B1") (pin "50") (pinfunction "50_50") (pintype "bidirectional"))
      (node (ref "DO") (pin "1") (pinfunction "1_1") (pintype "passive"))
    )
    (net (code "50") (name "/MOSI") (class "Default")
      (node (ref "B1") (pin "51") (pinfunction "51_51") (pintype "bidirectional"))
      (node (ref "DI") (pin "1") (pinfunction "1_1") (pintype "passive"))
    )
    (net (code "51") (name "/MRX") (class "Default")
      (node (ref "B1") (pin "0") (pinfunction "0(RX0)_0") (pintype "bidirectional"))
      (node (ref "OK1") (pin "6") (pinfunction "VO_6") (pintype "passive"))
      (node (ref "R25") (pin "P$2") (pinfunction "2_P$2") (pintype "passive"))
    )
    (net (code "52") (name "/MTX") (class "Default")
      (node (ref "B1") (pin "1") (pinfunction "1(TX0)_1") (pintype "bidirectional"))
      (node (ref "MIDI_OUT") (pin "3") (pinfunction "KL_3") (pintype "passive"))
    )
    (net (code "53") (name "/MZ1") (class "Default")
      (node (ref "B1") (pin "11") (pinfunction "11_11") (pintype "bidirectional"))
      (node (ref "R23") (pin "P$2") (pinfunction "2_P$2") (pintype "passive"))
    )
    (net (code "54") (name "/MZ2") (class "Default")
      (node (ref "B1") (pin "12") (pinfunction "12_12") (pintype "bidirectional"))
      (node (ref "R21") (pin "P$2") (pinfunction "2_P$2") (pintype "passive"))
      (node (ref "R22") (pin "P$2") (pinfunction "2_P$2") (pintype "passive"))
    )
    (net (code "55") (name "/RA") (class "Default")
      (node (ref "B1") (pin "49") (pinfunction "49_49") (pintype "bidirectional"))
      (node (ref "DRIGHT") (pin "7") (pinfunction "A_7") (pintype "passive"))
      (node (ref "RA") (pin "1") (pinfunction "1_1") (pintype "passive"))
    )
    (net (code "56") (name "/RB") (class "Default")
      (node (ref "B1") (pin "48") (pinfunction "48_48") (pintype "bidirectional"))
      (node (ref "DRIGHT") (pin "6") (pinfunction "B_6") (pintype "passive"))
      (node (ref "RB") (pin "1") (pinfunction "1_1") (pintype "passive"))
    )
    (net (code "57") (name "/RC") (class "Default")
      (node (ref "B1") (pin "47") (pinfunction "47_47") (pintype "bidirectional"))
      (node (ref "DRIGHT") (pin "4") (pinfunction "C_4") (pintype "passive"))
      (node (ref "RC") (pin "1") (pinfunction "1_1") (pintype "passive"))
    )
    (net (code "58") (name "/RD") (class "Default")
      (node (ref "B1") (pin "46") (pinfunction "46_46") (pintype "bidirectional"))
      (node (ref "DRIGHT") (pin "2") (pinfunction "D_2") (pintype "passive"))
      (node (ref "RD") (pin "1") (pinfunction "1_1") (pintype "passive"))
    )
    (net (code "59") (name "/RE") (class "Default")
      (node (ref "B1") (pin "45") (pinfunction "45_45") (pintype "bidirectional"))
      (node (ref "DRIGHT") (pin "1") (pinfunction "E_1") (pintype "passive"))
      (node (ref "RE") (pin "1") (pinfunction "1_1") (pintype "passive"))
    )
    (net (code "60") (name "/RF") (class "Default")
      (node (ref "B1") (pin "44") (pinfunction "44_44") (pintype "bidirectional"))
      (node (ref "DRIGHT") (pin "9") (pinfunction "F_9") (pintype "passive"))
      (node (ref "RF") (pin "1") (pinfunction "1_1") (pintype "passive"))
    )
    (net (code "61") (name "/RG") (class "Default")
      (node (ref "B1") (pin "43") (pinfunction "43_43") (pintype "bidirectional"))
      (node (ref "DRIGHT") (pin "10") (pinfunction "G_10") (pintype "passive"))
      (node (ref "RG") (pin "1") (pinfunction "1_1") (pintype "passive"))
    )
    (net (code "62") (name "/RP") (class "Default")
      (node (ref "B1") (pin "42") (pinfunction "42_42") (pintype "bidirectional"))
      (node (ref "DRIGHT") (pin "5") (pinfunction "DP_5") (pintype "passive"))
      (node (ref "RP") (pin "1") (pinfunction "1_1") (pintype "passive"))
    )
    (net (code "63") (name "/SCK") (class "Default")
      (node (ref "B1") (pin "52") (pinfunction "52_52") (pintype "bidirectional"))
      (node (ref "CLK") (pin "1") (pinfunction "1_1") (pintype "passive"))
    )
    (net (code "64") (name "/SS") (class "Default")
      (node (ref "B1") (pin "53") (pinfunction "53_53") (pintype "bidirectional"))
      (node (ref "CS") (pin "1") (pinfunction "1_1") (pintype "passive"))
    )
    (net (code "65") (name "GND") (class "Default")
      (node (ref "B1") (pin "GND@0") (pinfunction "GND_GND@0") (pintype "bidirectional"))
      (node (ref "B1") (pin "GND@1") (pinfunction "GND_GND@1") (pintype "bidirectional"))
      (node (ref "B1") (pin "GND@2") (pinfunction "GND_GND@2") (pintype "bidirectional"))
      (node (ref "B1") (pin "GND@3") (pinfunction "GND_GND@3") (pintype "bidirectional"))
      (node (ref "B1") (pin "GND@4") (pinfunction "GND_GND@4") (pintype "bidirectional"))
      (node (ref "C1") (pin "2") (pinfunction "2_2") (pintype "passive"))
      (node (ref "DLEFT") (pin "3") (pinfunction "CK1_3") (pintype "passive"))
      (node (ref "DLEFT") (pin "8") (pinfunction "CK2_8") (pintype "passive"))
      (node (ref "DRIGHT") (pin "3") (pinfunction "CK1_3") (pintype "passive"))
      (node (ref "DRIGHT") (pin "8") (pinfunction "CK2_8") (pintype "passive"))
      (node (ref "GND") (pin "1") (pinfunction "1_1") (pintype "passive"))
      (node (ref "JA") (pin "SLEEVE") (pinfunction "SLEEVE_SLEEVE") (pintype "passive"))
      (node (ref "LED1") (pin "K") (pinfunction "C_K") (pintype "passive"))
      (node (ref "LED2") (pin "K") (pinfunction "C_K") (pintype "passive"))
      (node (ref "LED3") (pin "K") (pinfunction "C_K") (pintype "passive"))
      (node (ref "LED4") (pin "K") (pinfunction "C_K") (pintype "passive"))
      (node (ref "LED5") (pin "K") (pinfunction "C_K") (pintype "passive"))
      (node (ref "LED6") (pin "K") (pinfunction "C_K") (pintype "passive"))
      (node (ref "LED7") (pin "K") (pinfunction "C_K") (pintype "passive"))
      (node (ref "MIDI_OUT") (pin "1") (pinfunction "KL_1") (pintype "passive"))
      (node (ref "OK1") (pin "5") (pinfunction "GND_5") (pintype "passive"))
      (node (ref "P1") (pin "1") (pinfunction "A_1") (pintype "passive"))
      (node (ref "P2") (pin "1") (pinfunction "A_1") (pintype "passive"))
      (node (ref "P3") (pin "1") (pinfunction "A_1") (pintype "passive"))
      (node (ref "P4") (pin "1") (pinfunction "A_1") (pintype "passive"))
      (node (ref "P5") (pin "1") (pinfunction "A_1") (pintype "passive"))
      (node (ref "P6") (pin "1") (pinfunction "A_1") (pintype "passive"))
      (node (ref "P7") (pin "1") (pinfunction "A_1") (pintype "passive"))
      (node (ref "P8") (pin "1") (pinfunction "A_1") (pintype "passive"))
      (node (ref "R26") (pin "P$2") (pinfunction "2_P$2") (pintype "passive"))
      (node (ref "RGB") (pin "2") (pinfunction "C_2") (pintype "bidirectional"))
      (node (ref "S1") (pin "A") (pinfunction "A_A") (pintype "passive"))
      (node (ref "SW1") (pin "P$1") (pinfunction "P$1_P$1") (pintype "passive"))
      (node (ref "SW2") (pin "P$1") (pinfunction "P$1_P$1") (pintype "passive"))
      (node (ref "SW3") (pin "P$1") (pinfunction "P$1_P$1") (pintype "passive"))
      (node (ref "SW4") (pin "P$1") (pinfunction "P$1_P$1") (pintype "passive"))
      (node (ref "SW5") (pin "P$1") (pinfunction "P$1_P$1") (pintype "passive"))
      (node (ref "SW6") (pin "P$1") (pinfunction "P$1_P$1") (pintype "passive"))
      (node (ref "SW7") (pin "P$1") (pinfunction "P$1_P$1") (pintype "passive"))
      (node (ref "SW8") (pin "P$1") (pinfunction "P$1_P$1") (pintype "passive"))
    )
    (net (code "66") (name "Net-(MIDI_INB-KL)") (class "Default")
      (node (ref "MIDI_IN") (pin "2") (pinfunction "KL_2") (pintype "passive"))
      (node (ref "R24") (pin "P$2") (pinfunction "2_P$2") (pintype "passive"))
    )
    (net (code "67") (name "Net-(MIDI_INC-KL)") (class "Default")
      (node (ref "D1") (pin "A") (pinfunction "A_A") (pintype "passive"))
      (node (ref "MIDI_IN") (pin "3") (pinfunction "KL_3") (pintype "passive"))
      (node (ref "OK1") (pin "3") (pinfunction "C_3") (pintype "passive"))
    )
    (net (code "68") (name "Net-(MIDI_OUTB-KL)") (class "Default")
      (node (ref "MIDI_OUT") (pin "2") (pinfunction "KL_2") (pintype "passive"))
      (node (ref "R27") (pin "P$2") (pinfunction "2_P$2") (pintype "passive"))
    )
    (net (code "69") (name "Net-(OK1-A)") (class "Default")
      (node (ref "D1") (pin "C") (pinfunction "C_C") (pintype "passive"))
      (node (ref "OK1") (pin "2") (pinfunction "A_2") (pintype "passive"))
      (node (ref "R24") (pin "P$1") (pinfunction "1_P$1") (pintype "passive"))
    )
    (net (code "70") (name "Net-(OK1-VB)") (class "Default")
      (node (ref "OK1") (pin "7") (pinfunction "VB_7") (pintype "passive"))
      (node (ref "R26") (pin "P$1") (pinfunction "1_P$1") (pintype "passive"))
    )
    (net (code "71") (name "Net-(R9-1)") (class "Default")
      (node (ref "R9") (pin "P$1") (pinfunction "1_P$1") (pintype "passive"))
      (node (ref "S1") (pin "1") (pinfunction "1_1") (pintype "passive"))
    )
    (net (code "72") (name "Net-(R10-1)") (class "Default")
      (node (ref "R10") (pin "P$1") (pinfunction "1_P$1") (pintype "passive"))
      (node (ref "S1") (pin "2") (pinfunction "2_2") (pintype "passive"))
    )
    (net (code "73") (name "Net-(R11-1)") (class "Default")
      (node (ref "R11") (pin "P$1") (pinfunction "1_P$1") (pintype "passive"))
      (node (ref "S1") (pin "3") (pinfunction "3_3") (pintype "passive"))
    )
    (net (code "74") (name "Net-(R12-1)") (class "Default")
      (node (ref "R12") (pin "P$1") (pinfunction "1_P$1") (pintype "passive"))
      (node (ref "S1") (pin "4") (pinfunction "4_4") (pintype "passive"))
    )
    (net (code "75") (name "Net-(R13-1)") (class "Default")
      (node (ref "R13") (pin "P$1") (pinfunction "1_P$1") (pintype "passive"))
      (node (ref "S1") (pin "5") (pinfunction "5_5") (pintype "passive"))
    )
    (net (code "76") (name "Net-(R14-1)") (class "Default")
      (node (ref "R14") (pin "P$1") (pinfunction "1_P$1") (pintype "passive"))
      (node (ref "S1") (pin "6") (pinfunction "6_6") (pintype "passive"))
    )
    (net (code "77") (name "Net-(R15-1)") (class "Default")
      (node (ref "R15") (pin "P$1") (pinfunction "1_P$1") (pintype "passive"))
      (node (ref "S1") (pin "7") (pinfunction "7_7") (pintype "passive"))
    )
    (net (code "78") (name "Net-(R16-1)") (class "Default")
      (node (ref "R16") (pin "P$1") (pinfunction "1_P$1") (pintype "passive"))
      (node (ref "S1") (pin "8") (pinfunction "8_8") (pintype "passive"))
    )
    (net (code "79") (name "Net-(R17-1)") (class "Default")
      (node (ref "R17") (pin "P$1") (pinfunction "1_P$1") (pintype "passive"))
      (node (ref "S1") (pin "9") (pinfunction "9_9") (pintype "passive"))
    )
    (net (code "80") (name "Net-(R18-1)") (class "Default")
      (node (ref "R18") (pin "P$1") (pinfunction "1_P$1") (pintype "passive"))
      (node (ref "S1") (pin "10") (pinfunction "10_10") (pintype "passive"))
    )
    (net (code "81") (name "Net-(R19-1)") (class "Default")
      (node (ref "R19") (pin "P$1") (pinfunction "1_P$1") (pintype "passive"))
      (node (ref "S1") (pin "11") (pinfunction "11_11") (pintype "passive"))
    )
    (net (code "82") (name "Net-(R20-1)") (class "Default")
      (node (ref "R20") (pin "P$1") (pinfunction "1_P$1") (pintype "passive"))
      (node (ref "S1") (pin "12") (pinfunction "12_12") (pintype "passive"))
    )
    (net (code "83") (name "unconnected-(3V3-Pad1)") (class "Default")
      (node (ref "3V3") (pin "1") (pinfunction "1_1") (pintype "passive"))
    )
    (net (code "84") (name "unconnected-(B1-14(TX3)-Pad14)") (class "Default")
      (node (ref "B1") (pin "14") (pinfunction "14(TX3)_14") (pintype "bidirectional"))
    )
    (net (code "85") (name "unconnected-(B1-15(RX3)-Pad15)") (class "Default")
      (node (ref "B1") (pin "15") (pinfunction "15(RX3)_15") (pintype "bidirectional"))
    )
    (net (code "86") (name "unconnected-(B1-Pad3.3V)") (class "Default")
      (node (ref "B1") (pin "3.3V") (pinfunction "3.3V_3.3V") (pintype "bidirectional"))
    )
    (net (code "87") (name "unconnected-(B1-Pad4)") (class "Default")
      (node (ref "B1") (pin "4") (pinfunction "4_4") (pintype "bidirectional"))
    )
    (net (code "88") (name "unconnected-(B1-Pad13)") (class "Default")
      (node (ref "B1") (pin "13") (pinfunction "13_13") (pintype "bidirectional"))
    )
    (net (code "89") (name "unconnected-(B1-Pad38)") (class "Default")
      (node (ref "B1") (pin "38") (pinfunction "38_38") (pintype "bidirectional"))
    )
    (net (code "90") (name "unconnected-(B1-Pad39)") (class "Default")
      (node (ref "B1") (pin "39") (pinfunction "39_39") (pintype "bidirectional"))
    )
    (net (code "91") (name "unconnected-(B1-Pad40)") (class "Default")
      (node (ref "B1") (pin "40") (pinfunction "40_40") (pintype "bidirectional"))
    )
    (net (code "92") (name "unconnected-(B1-Pad41)") (class "Default")
      (node (ref "B1") (pin "41") (pinfunction "41_41") (pintype "bidirectional"))
    )
    (net (code "93") (name "unconnected-(B1-PadA7)") (class "Default")
      (node (ref "B1") (pin "A7") (pinfunction "A7_A7") (pintype "bidirectional"))
    )
    (net (code "94") (name "unconnected-(B1-PadAREF)") (class "Default")
      (node (ref "B1") (pin "AREF") (pinfunction "AREF_AREF") (pintype "bidirectional"))
    )
    (net (code "95") (name "unconnected-(B1-PadRESET)") (class "Default")
      (node (ref "B1") (pin "RESET") (pinfunction "RESET_RESET") (pintype "bidirectional"))
    )
    (net (code "96") (name "unconnected-(B1-PadVIN)") (class "Default")
      (node (ref "B1") (pin "VIN") (pinfunction "VIN_VIN") (pintype "bidirectional"))
    )
    (net (code "97") (name "unconnected-(CD-Pad1)") (class "Default")
      (node (ref "CD") (pin "1") (pinfunction "1_1") (pintype "passive"))
    )
    (net (code "98") (name "unconnected-(MIDI_INA-KL-Pad1)") (class "Default")
      (node (ref "MIDI_IN") (pin "1") (pinfunction "KL_1") (pintype "passive"))
    )
  )
)
